# CapstoneMCU.net
KiCad netlist of a schematic drawn in EasyEDA Pro
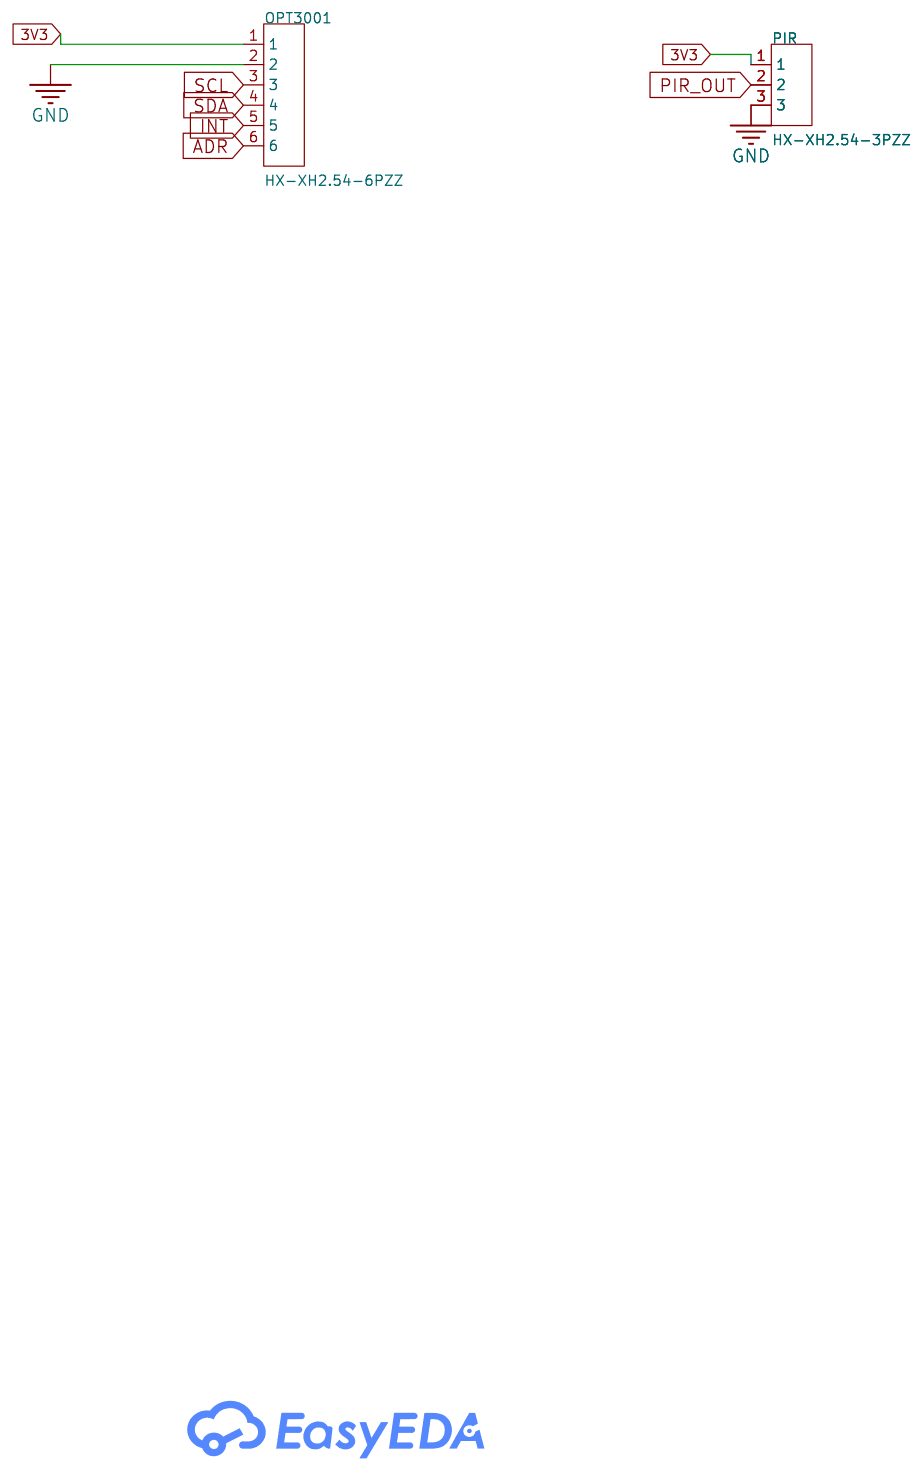
[diagram p0: sensors]
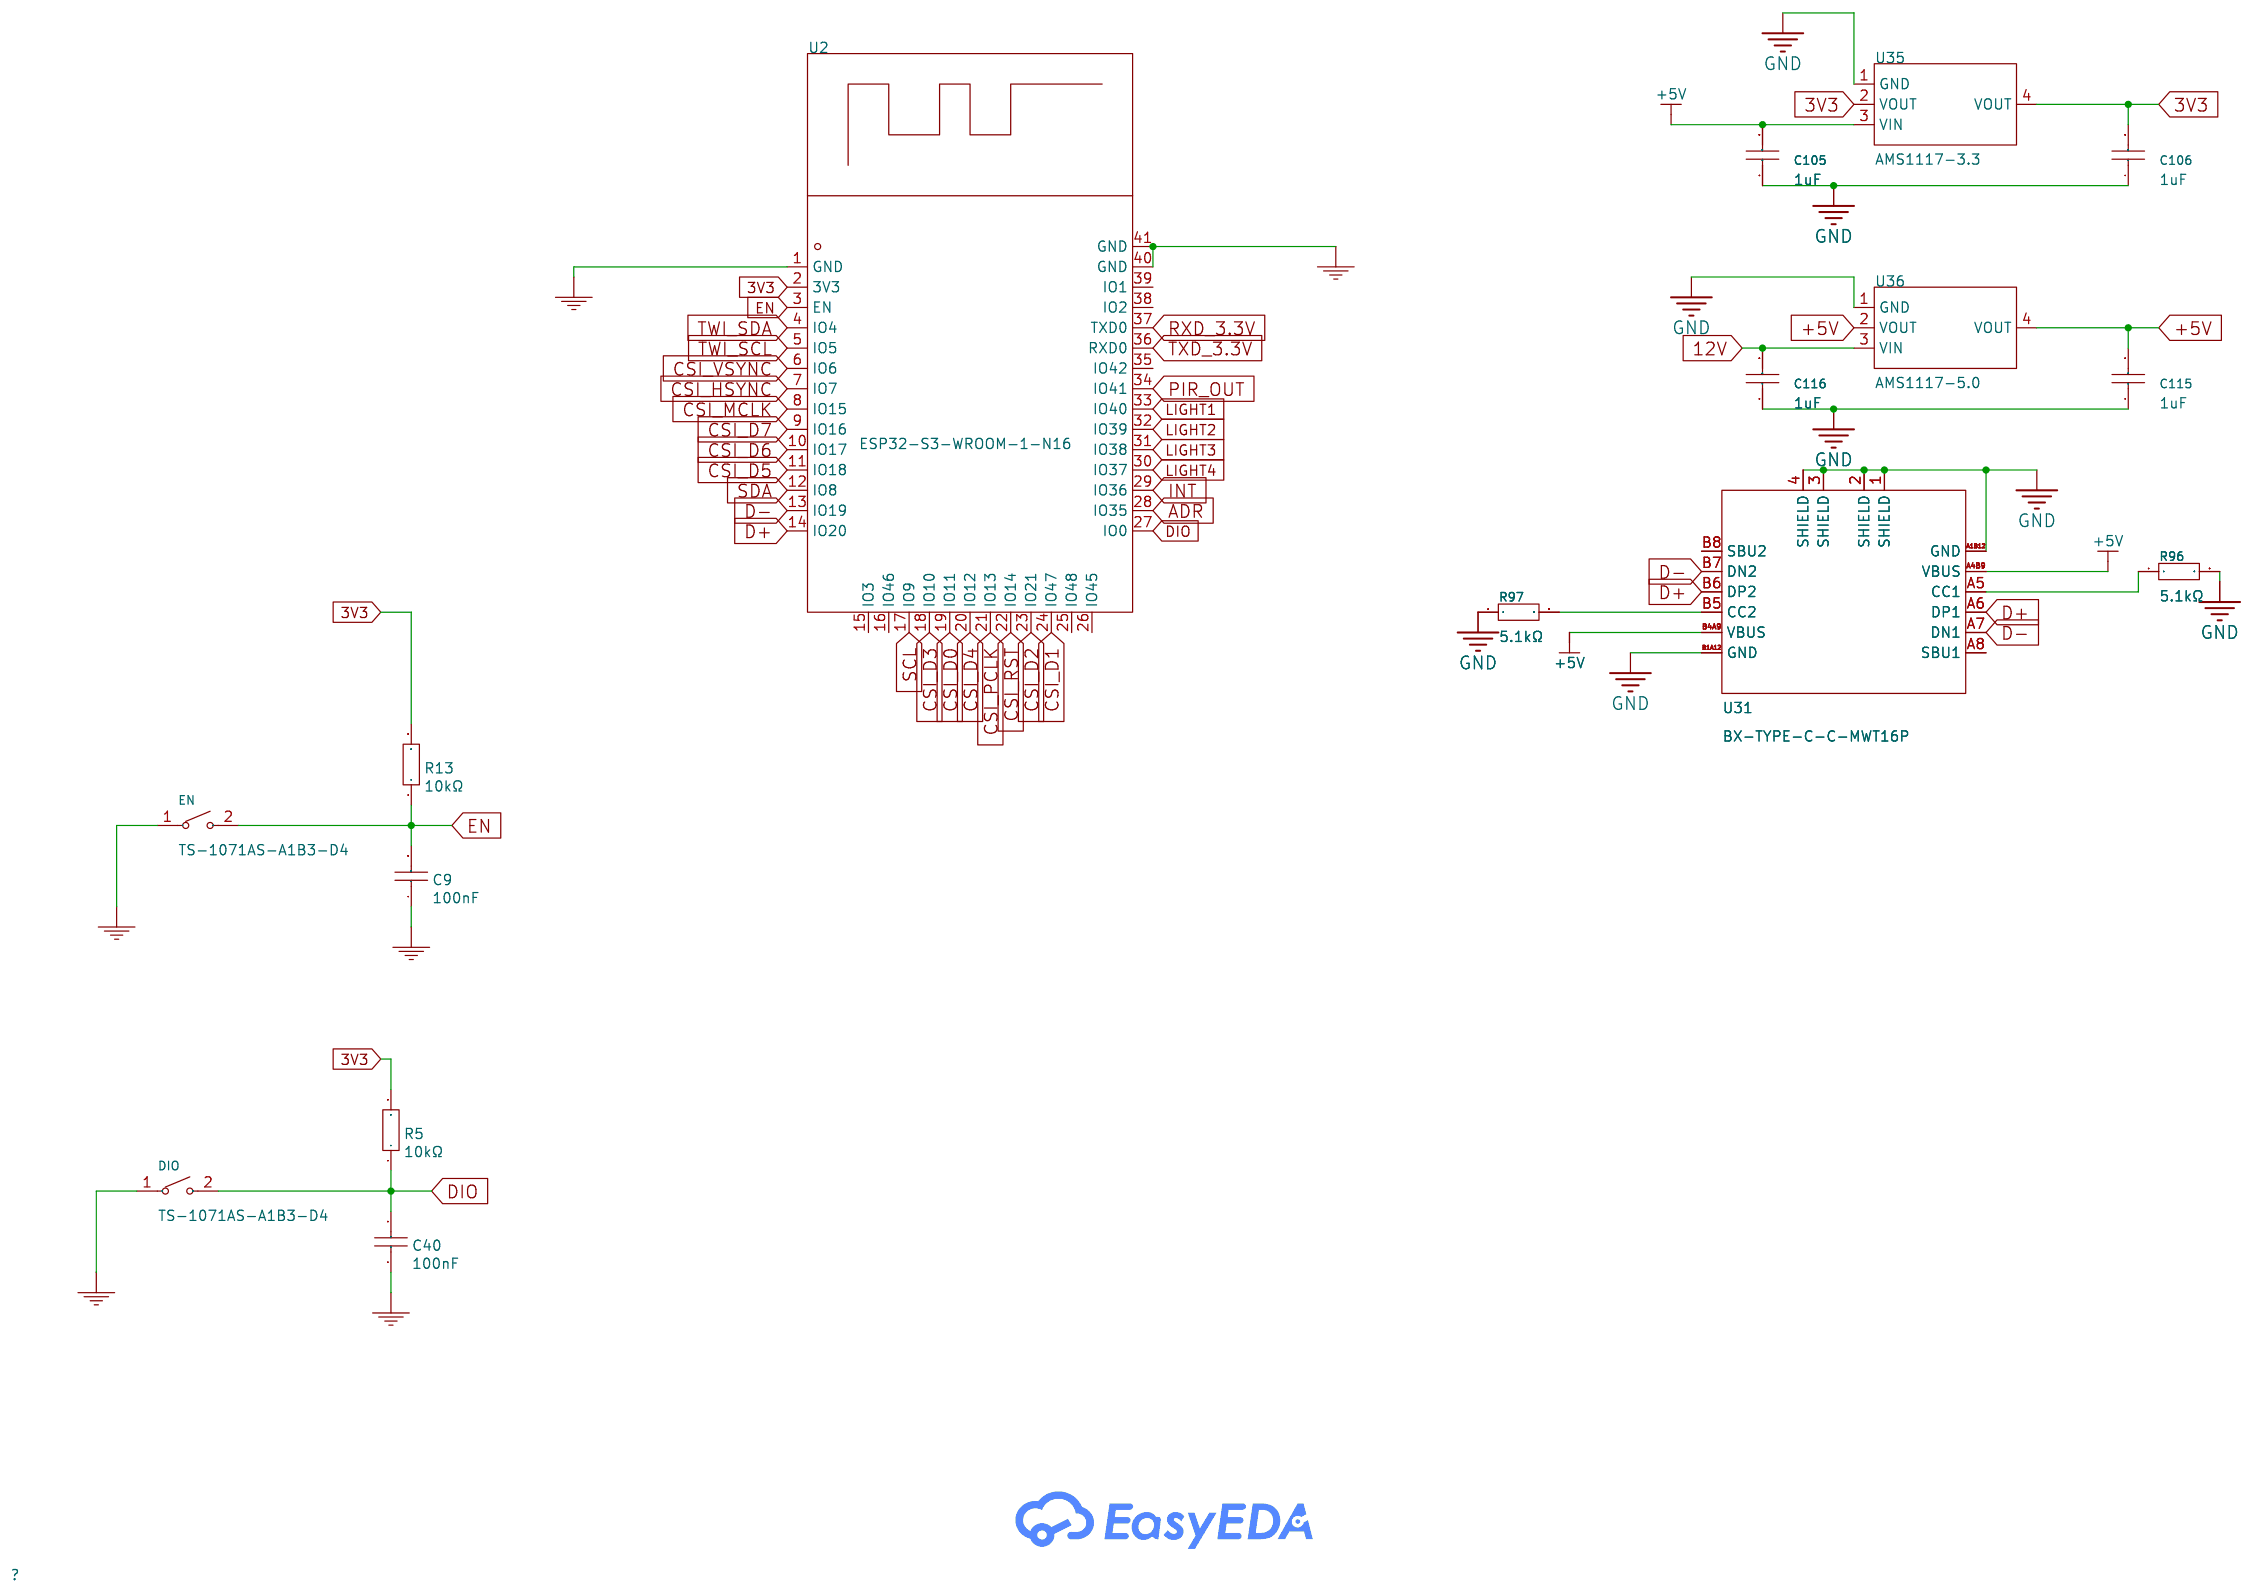
[diagram p1: ESP32-S3]
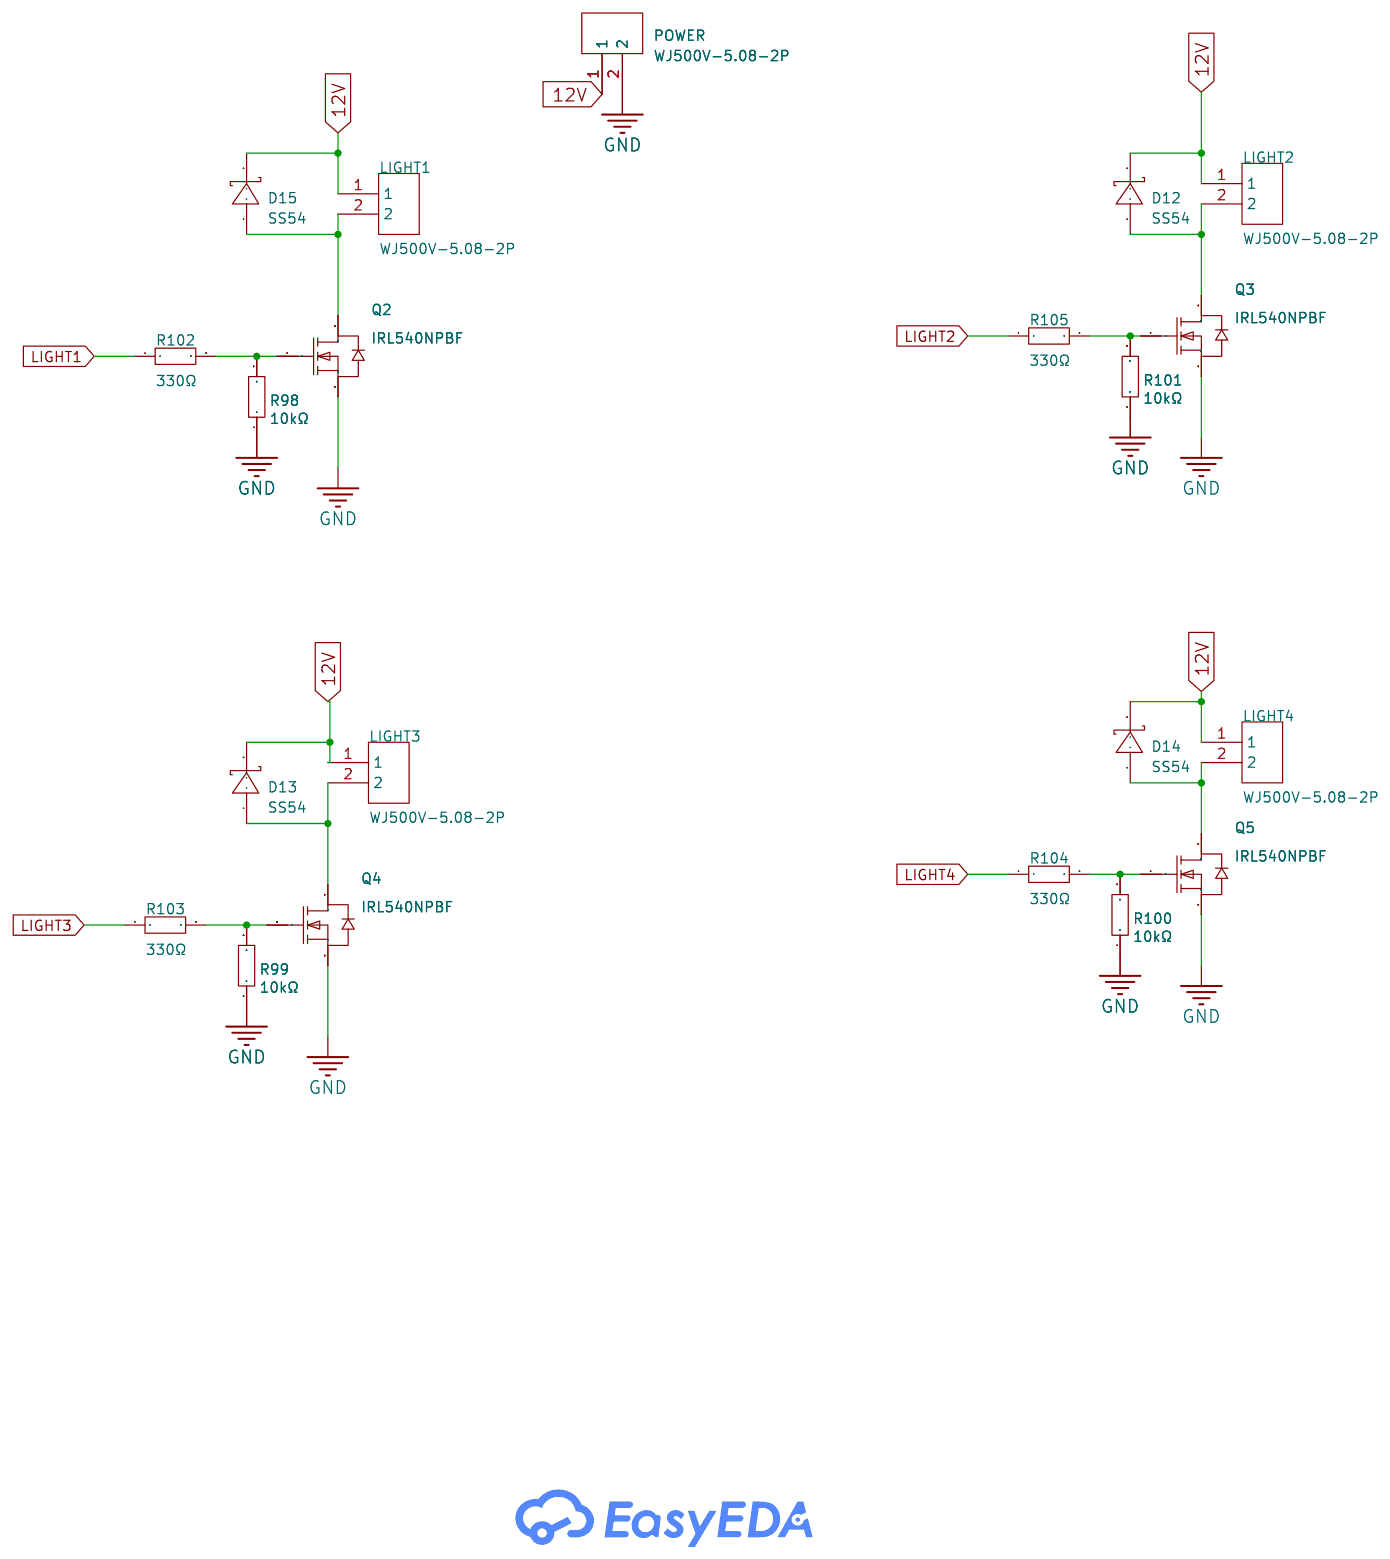
[diagram p2: MOSFET]
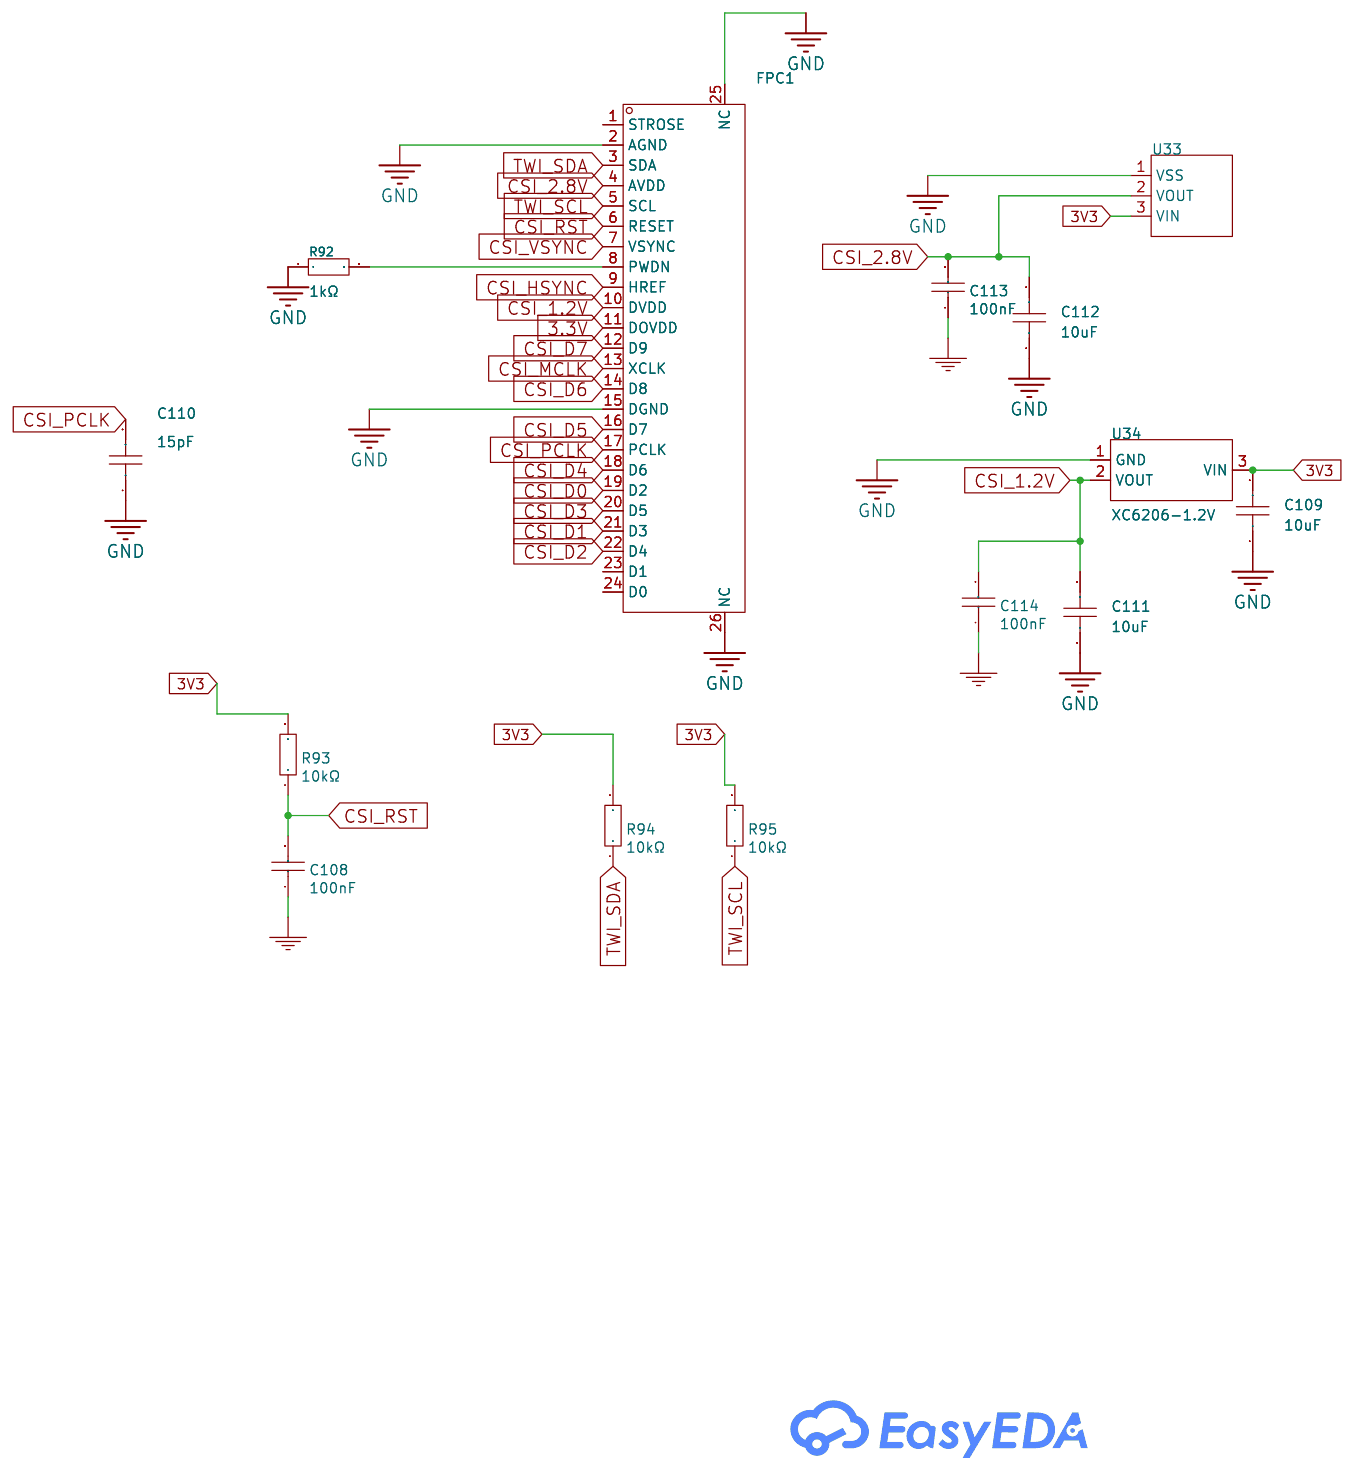
[diagram p3: camera]

(export (version "E")
  (design (tool "Eeschema 10.0.6"))
  (components
    (comp (ref "OPT3001")
      (value "HX-XH2.54-6PZZ")
      (footprint "easyedapro:CONN-TH_6P-P2.50_BX-XH2.54-6PZZ")
      (fields (field (name "Manufacturer") "hanxia(韩下)"))
      (libsource (lib "easyedapro") (part "HX-XH2.54-6PZZ"))
    )
    (comp (ref "PIR")
      (value "HX-XH2.54-3PZZ")
      (footprint "easyedapro:CONN-TH_3P-P2.50_HC-XH-3A-G")
      (fields (field (name "Manufacturer") "hanxia(韩下)"))
      (libsource (lib "easyedapro") (part "HX-XH2.54-3PZZ"))
    )
    (comp (ref "C9")
      (value "100nF")
      (footprint "easyedapro:C0402_NEW")
      (fields (field (name "Manufacturer Part") "CL05B104KO5NNNC") (field (name "Manufacturer") "SAMSUNG"))
      (libsource (lib "easyedapro") (part "100nF"))
    )
    (comp (ref "C40")
      (value "100nF")
      (footprint "easyedapro:C0402_NEW")
      (fields (field (name "Manufacturer Part") "CL05B104KO5NNNC") (field (name "Manufacturer") "SAMSUNG"))
      (libsource (lib "easyedapro") (part "100nF"))
    )
    (comp (ref "C105")
      (value "1uF")
      (footprint "easyedapro:C0402")
      (fields
        (field (name "Manufacturer Part") "CL05A105KP5NNNC")
        (field (name "Manufacturer") "SAMSUNG(三星)")
      )
      (libsource (lib "easyedapro") (part "CL05A105KP5NNNC"))
    )
    (comp (ref "C106")
      (value "1uF")
      (footprint "easyedapro:C0402")
      (fields
        (field (name "Manufacturer Part") "CL05A105KP5NNNC")
        (field (name "Manufacturer") "SAMSUNG(三星)")
      )
      (libsource (lib "easyedapro") (part "CL05A105KP5NNNC"))
    )
    (comp (ref "C115")
      (value "1uF")
      (footprint "easyedapro:C0402")
      (fields
        (field (name "Manufacturer Part") "CL05A105KP5NNNC")
        (field (name "Manufacturer") "SAMSUNG(三星)")
      )
      (libsource (lib "easyedapro") (part "CL05A105KP5NNNC"))
    )
    (comp (ref "C116")
      (value "1uF")
      (footprint "easyedapro:C0402")
      (fields
        (field (name "Manufacturer Part") "CL05A105KP5NNNC")
        (field (name "Manufacturer") "SAMSUNG(三星)")
      )
      (libsource (lib "easyedapro") (part "CL05A105KP5NNNC"))
    )
    (comp (ref "DIO")
      (value "TS-1071AS-A1B3-D4")
      (footprint "easyedapro:SW-SMD_L4.0-W3.0-LS4.8")
      (fields (field (name "Manufacturer") "Yuandi(元迪)"))
      (libsource (lib "easyedapro") (part "TS-1071AS-A1B3-D4"))
    )
    (comp (ref "EN")
      (value "TS-1071AS-A1B3-D4")
      (footprint "easyedapro:SW-SMD_L4.0-W3.0-LS4.8")
      (fields (field (name "Manufacturer") "Yuandi(元迪)"))
      (libsource (lib "easyedapro") (part "TS-1071AS-A1B3-D4"))
    )
    (comp (ref "R5")
      (value "10kΩ")
      (footprint "easyedapro:R0402")
      (fields (field (name "Manufacturer Part") "0402WGF1002TCE") (field (name "Manufacturer") "UniOhm"))
      (libsource (lib "easyedapro") (part "10kΩ"))
    )
    (comp (ref "R13")
      (value "10kΩ")
      (footprint "easyedapro:R0402")
      (fields (field (name "Manufacturer Part") "0402WGF1002TCE") (field (name "Manufacturer") "UniOhm"))
      (libsource (lib "easyedapro") (part "10kΩ"))
    )
    (comp (ref "R96")
      (value "5.1kΩ")
      (footprint "easyedapro:R0402")
      (fields
        (field (name "Manufacturer Part") "0402WGF5101TCE")
        (field (name "Manufacturer") "UNI-ROYAL(厚声)")
      )
      (libsource (lib "easyedapro") (part "0402WGF5101TCE"))
    )
    (comp (ref "R97")
      (value "5.1kΩ")
      (footprint "easyedapro:R0402")
      (fields
        (field (name "Manufacturer Part") "0402WGF5101TCE")
        (field (name "Manufacturer") "UNI-ROYAL(厚声)")
      )
      (libsource (lib "easyedapro") (part "0402WGF5101TCE"))
    )
    (comp (ref "U2")
      (value "ESP32-S3-WROOM-1-N16")
      (footprint "easyedapro:WIRELM-SMD_ESP32-S3-WROOM-1")
      (fields (field (name "Manufacturer") "ESPRESSIF(乐鑫)"))
      (libsource (lib "easyedapro") (part "ESP32-S3-WROOM-1(N16)"))
    )
    (comp (ref "U31")
      (value "BX-TYPE-C-C-MWT16P")
      (footprint "easyedapro:USB-C-SMD_BX-TYPE-C-C-MWT16P")
      (fields (field (name "Manufacturer") "Bossie(博锡)"))
      (libsource (lib "easyedapro") (part "BX-TYPE-C-C-MWT16P"))
    )
    (comp (ref "U35")
      (value "AMS1117-3.3")
      (footprint "easyedapro:SOT-223-3_L6.5-W3.4-P2.30-LS7.0-BR")
      (fields (field (name "Manufacturer") "AMS"))
      (libsource (lib "easyedapro") (part "AMS1117-3.3"))
    )
    (comp (ref "U36")
      (value "AMS1117-5.0")
      (footprint "easyedapro:SOT-223_L6.5-W3.5-P2.30-LS7.0-BR")
      (fields (field (name "Manufacturer") "AMS"))
      (libsource (lib "easyedapro") (part "AMS1117-5.0"))
    )
    (comp (ref "D12")
      (value "SS54")
      (footprint "easyedapro:SMA_L4.4-W2.8-LS5.4-R-RD")
      (fields (field (name "Manufacturer") "MDD(辰达半导体)"))
      (libsource (lib "easyedapro") (part "SS54_C22452"))
    )
    (comp (ref "D13")
      (value "SS54")
      (footprint "easyedapro:SMA_L4.4-W2.8-LS5.4-R-RD")
      (fields (field (name "Manufacturer") "MDD(辰达半导体)"))
      (libsource (lib "easyedapro") (part "SS54_C22452"))
    )
    (comp (ref "D14")
      (value "SS54")
      (footprint "easyedapro:SMA_L4.4-W2.8-LS5.4-R-RD")
      (fields (field (name "Manufacturer") "MDD(辰达半导体)"))
      (libsource (lib "easyedapro") (part "SS54_C22452"))
    )
    (comp (ref "D15")
      (value "SS54")
      (footprint "easyedapro:SMA_L4.4-W2.8-LS5.4-R-RD")
      (fields (field (name "Manufacturer") "MDD(辰达半导体)"))
      (libsource (lib "easyedapro") (part "SS54_C22452"))
    )
    (comp (ref "LIGHT1")
      (value "WJ500V-5.08-2P")
      (footprint "easyedapro:CONN-TH_2P-P5.00_WJ500V-5.08-2P")
      (fields (field (name "Manufacturer") "KANGNEX(康奈克斯电气)"))
      (libsource (lib "easyedapro") (part "WJ500V-5.08-2P-14-00A"))
    )
    (comp (ref "LIGHT2")
      (value "WJ500V-5.08-2P")
      (footprint "easyedapro:CONN-TH_2P-P5.00_WJ500V-5.08-2P")
      (fields (field (name "Manufacturer") "KANGNEX(康奈克斯电气)"))
      (libsource (lib "easyedapro") (part "WJ500V-5.08-2P-14-00A"))
    )
    (comp (ref "LIGHT3")
      (value "WJ500V-5.08-2P")
      (footprint "easyedapro:CONN-TH_2P-P5.00_WJ500V-5.08-2P")
      (fields (field (name "Manufacturer") "KANGNEX(康奈克斯电气)"))
      (libsource (lib "easyedapro") (part "WJ500V-5.08-2P-14-00A"))
    )
    (comp (ref "LIGHT4")
      (value "WJ500V-5.08-2P")
      (footprint "easyedapro:CONN-TH_2P-P5.00_WJ500V-5.08-2P")
      (fields (field (name "Manufacturer") "KANGNEX(康奈克斯电气)"))
      (libsource (lib "easyedapro") (part "WJ500V-5.08-2P-14-00A"))
    )
    (comp (ref "POWER")
      (value "WJ500V-5.08-2P")
      (footprint "easyedapro:CONN-TH_2P-P5.00_WJ500V-5.08-2P")
      (fields (field (name "Manufacturer") "KANGNEX(康奈克斯电气)"))
      (libsource (lib "easyedapro") (part "WJ500V-5.08-2P-14-00A"))
    )
    (comp (ref "Q2")
      (value "IRL540NPBF")
      (footprint "easyedapro:TO-220-3_L10.0-W4.5-P2.54-T")
      (fields (field (name "Manufacturer") "Infineon(英飞凌)"))
      (libsource (lib "easyedapro") (part "IRL540NPBF"))
    )
    (comp (ref "Q3")
      (value "IRL540NPBF")
      (footprint "easyedapro:TO-220-3_L10.0-W4.5-P2.54-T")
      (fields (field (name "Manufacturer") "Infineon(英飞凌)"))
      (libsource (lib "easyedapro") (part "IRL540NPBF"))
    )
    (comp (ref "Q4")
      (value "IRL540NPBF")
      (footprint "easyedapro:TO-220-3_L10.0-W4.5-P2.54-T")
      (fields (field (name "Manufacturer") "Infineon(英飞凌)"))
      (libsource (lib "easyedapro") (part "IRL540NPBF"))
    )
    (comp (ref "Q5")
      (value "IRL540NPBF")
      (footprint "easyedapro:TO-220-3_L10.0-W4.5-P2.54-T")
      (fields (field (name "Manufacturer") "Infineon(英飞凌)"))
      (libsource (lib "easyedapro") (part "IRL540NPBF"))
    )
    (comp (ref "R98")
      (value "10kΩ")
      (footprint "easyedapro:R0402")
      (fields (field (name "Manufacturer Part") "0402WGF1002TCE") (field (name "Manufacturer") "UniOhm"))
      (libsource (lib "easyedapro") (part "10kΩ"))
    )
    (comp (ref "R99")
      (value "10kΩ")
      (footprint "easyedapro:R0402")
      (fields (field (name "Manufacturer Part") "0402WGF1002TCE") (field (name "Manufacturer") "UniOhm"))
      (libsource (lib "easyedapro") (part "10kΩ"))
    )
    (comp (ref "R100")
      (value "10kΩ")
      (footprint "easyedapro:R0402")
      (fields (field (name "Manufacturer Part") "0402WGF1002TCE") (field (name "Manufacturer") "UniOhm"))
      (libsource (lib "easyedapro") (part "10kΩ"))
    )
    (comp (ref "R101")
      (value "10kΩ")
      (footprint "easyedapro:R0402")
      (fields (field (name "Manufacturer Part") "0402WGF1002TCE") (field (name "Manufacturer") "UniOhm"))
      (libsource (lib "easyedapro") (part "10kΩ"))
    )
    (comp (ref "R102")
      (value "330Ω")
      (footprint "easyedapro:R0402")
      (fields (field (name "Manufacturer Part") "RC0402FR-07330RL") (field (name "Manufacturer") "YAGEO(国巨)"))
      (libsource (lib "easyedapro") (part "RC0402FR-07330RL"))
    )
    (comp (ref "R103")
      (value "330Ω")
      (footprint "easyedapro:R0402")
      (fields (field (name "Manufacturer Part") "RC0402FR-07330RL") (field (name "Manufacturer") "YAGEO(国巨)"))
      (libsource (lib "easyedapro") (part "RC0402FR-07330RL"))
    )
    (comp (ref "R104")
      (value "330Ω")
      (footprint "easyedapro:R0402")
      (fields (field (name "Manufacturer Part") "RC0402FR-07330RL") (field (name "Manufacturer") "YAGEO(国巨)"))
      (libsource (lib "easyedapro") (part "RC0402FR-07330RL"))
    )
    (comp (ref "R105")
      (value "330Ω")
      (footprint "easyedapro:R0402")
      (fields (field (name "Manufacturer Part") "RC0402FR-07330RL") (field (name "Manufacturer") "YAGEO(国巨)"))
      (libsource (lib "easyedapro") (part "RC0402FR-07330RL"))
    )
    (comp (ref "C108")
      (value "100nF")
      (footprint "easyedapro:C0402_NEW")
      (fields (field (name "Manufacturer Part") "CL05B104KO5NNNC") (field (name "Manufacturer") "SAMSUNG"))
      (libsource (lib "easyedapro") (part "100nF"))
    )
    (comp (ref "C109")
      (value "10uF")
      (footprint "easyedapro:C0402")
      (description "Capacitance:10uF Tolerance:±20% Tolerance:±20% Voltage Rating:10V Temperature Coefficient:X5R")
      (fields
        (field (name "Manufacturer Part") "CL05A106MP5NUNC")
        (field (name "Manufacturer") "SAMSUNG(三星)")
      )
      (libsource (lib "easyedapro") (part "CL05A106MP5NUNC_C315248"))
    )
    (comp (ref "C110")
      (value "15pF")
      (footprint "easyedapro:C0402")
      (description "Capacitance:15pF Tolerance:±5% Tolerance:±5% Voltage Rating:50V Temperature Coefficient:C0G")
      (fields
        (field (name "Manufacturer Part") "CL05C150JB5NNNC")
        (field (name "Manufacturer") "SAMSUNG(三星)")
      )
      (libsource (lib "easyedapro") (part "CL05C150JB5NNNC"))
    )
    (comp (ref "C111")
      (value "10uF")
      (footprint "easyedapro:C0402")
      (description "Capacitance:10uF Tolerance:±20% Tolerance:±20% Voltage Rating:10V Temperature Coefficient:X5R")
      (fields
        (field (name "Manufacturer Part") "CL05A106MP5NUNC")
        (field (name "Manufacturer") "SAMSUNG(三星)")
      )
      (libsource (lib "easyedapro") (part "CL05A106MP5NUNC_C315248"))
    )
    (comp (ref "C112")
      (value "10uF")
      (footprint "easyedapro:C0402")
      (description "Capacitance:10uF Tolerance:±20% Tolerance:±20% Voltage Rating:10V Temperature Coefficient:X5R")
      (fields
        (field (name "Manufacturer Part") "CL05A106MP5NUNC")
        (field (name "Manufacturer") "SAMSUNG(三星)")
      )
      (libsource (lib "easyedapro") (part "CL05A106MP5NUNC_C315248"))
    )
    (comp (ref "C113")
      (value "100nF")
      (footprint "easyedapro:C0402_NEW")
      (fields (field (name "Manufacturer Part") "CL05B104KO5NNNC") (field (name "Manufacturer") "SAMSUNG"))
      (libsource (lib "easyedapro") (part "100nF"))
    )
    (comp (ref "C114")
      (value "100nF")
      (footprint "easyedapro:C0402_NEW")
      (fields (field (name "Manufacturer Part") "CL05B104KO5NNNC") (field (name "Manufacturer") "SAMSUNG"))
      (libsource (lib "easyedapro") (part "100nF"))
    )
    (comp (ref "FPC1")
      (value "~")
      (footprint "easyedapro:FPC-SMD_P0.50-24P_XJ-FGS")
      (libsource (lib "easyedapro") (part "OV2640"))
    )
    (comp (ref "R92")
      (value "1kΩ")
      (footprint "easyedapro:R0402")
      (fields
        (field (name "Manufacturer Part") "0402WGF1001TCE")
        (field (name "Manufacturer") "UNI-ROYAL(厚声)")
      )
      (libsource (lib "easyedapro") (part "0402WGF1001TCE"))
    )
    (comp (ref "R93")
      (value "10kΩ")
      (footprint "easyedapro:R0402")
      (fields (field (name "Manufacturer Part") "0402WGF1002TCE") (field (name "Manufacturer") "UniOhm"))
      (libsource (lib "easyedapro") (part "10kΩ"))
    )
    (comp (ref "R94")
      (value "10kΩ")
      (footprint "easyedapro:R0402")
      (fields (field (name "Manufacturer Part") "0402WGF1002TCE") (field (name "Manufacturer") "UniOhm"))
      (libsource (lib "easyedapro") (part "10kΩ"))
    )
    (comp (ref "R95")
      (value "10kΩ")
      (footprint "easyedapro:R0402")
      (fields (field (name "Manufacturer Part") "0402WGF1002TCE") (field (name "Manufacturer") "UniOhm"))
      (libsource (lib "easyedapro") (part "10kΩ"))
    )
    (comp (ref "U33")
      (value "XC6206-2.8V")
      (footprint "easyedapro:SOT-23-3_L2.9-W1.6-P1.90-LS2.8-BR")
      (fields (field (name "Manufacturer") "YONGYUTAI(永裕泰)"))
      (libsource (lib "easyedapro") (part "XC6206-2.8V"))
    )
    (comp (ref "U34")
      (value "XC6206-1.2V")
      (footprint "easyedapro:SOT-23-3_L3.0-W1.6-P1.90-LS2.8-BR")
      (fields (field (name "Manufacturer") "YONGYUTAI(永裕泰)"))
      (libsource (lib "easyedapro") (part "XC6206-1.2V_C49446790"))
    )
  )
  (nets
    (net (code "1") (name "+5V") (class "Default")
      (node (ref "C105") (pin "2") (pinfunction "2_2") (pintype "input"))
      (node (ref "C115") (pin "2") (pinfunction "2_2") (pintype "input"))
      (node (ref "U31") (pin "A4B9") (pinfunction "VBUS_A4B9") (pintype "unspecified"))
      (node (ref "U31") (pin "B4A9") (pinfunction "VBUS_B4A9") (pintype "unspecified"))
      (node (ref "U35") (pin "3") (pinfunction "VIN_3") (pintype "unspecified"))
      (node (ref "U36") (pin "2") (pinfunction "VOUT_2") (pintype "unspecified"))
      (node (ref "U36") (pin "4") (pinfunction "VOUT_4") (pintype "unspecified"))
    )
    (net (code "2") (name "3.3V") (class "Default")
      (node (ref "FPC1") (pin "11") (pinfunction "DOVDD_11") (pintype "input"))
    )
    (net (code "3") (name "3V3") (class "Default")
      (node (ref "C106") (pin "2") (pinfunction "2_2") (pintype "input"))
      (node (ref "C109") (pin "2") (pinfunction "2_2") (pintype "unspecified"))
      (node (ref "OPT3001") (pin "1") (pinfunction "1_1") (pintype "unspecified"))
      (node (ref "PIR") (pin "1") (pinfunction "1_1") (pintype "unspecified"))
      (node (ref "R13") (pin "2") (pinfunction "2_2") (pintype "input"))
      (node (ref "R5") (pin "2") (pinfunction "2_2") (pintype "input"))
      (node (ref "R93") (pin "2") (pinfunction "2_2") (pintype "input"))
      (node (ref "R94") (pin "2") (pinfunction "2_2") (pintype "input"))
      (node (ref "R95") (pin "2") (pinfunction "2_2") (pintype "input"))
      (node (ref "U2") (pin "2") (pinfunction "3V3_2") (pintype "unspecified"))
      (node (ref "U33") (pin "3") (pinfunction "VIN_3") (pintype "unspecified"))
      (node (ref "U34") (pin "3") (pinfunction "VIN_3") (pintype "unspecified"))
      (node (ref "U35") (pin "2") (pinfunction "VOUT_2") (pintype "unspecified"))
      (node (ref "U35") (pin "4") (pinfunction "VOUT_4") (pintype "unspecified"))
    )
    (net (code "4") (name "12V") (class "Default")
      (node (ref "C116") (pin "2") (pinfunction "2_2") (pintype "input"))
      (node (ref "D12") (pin "2") (pinfunction "K_2") (pintype "unspecified"))
      (node (ref "D13") (pin "2") (pinfunction "K_2") (pintype "unspecified"))
      (node (ref "D14") (pin "2") (pinfunction "K_2") (pintype "unspecified"))
      (node (ref "D15") (pin "2") (pinfunction "K_2") (pintype "unspecified"))
      (node (ref "LIGHT1") (pin "1") (pinfunction "1_1") (pintype "unspecified"))
      (node (ref "LIGHT2") (pin "1") (pinfunction "1_1") (pintype "unspecified"))
      (node (ref "LIGHT3") (pin "1") (pinfunction "1_1") (pintype "unspecified"))
      (node (ref "LIGHT4") (pin "1") (pinfunction "1_1") (pintype "unspecified"))
      (node (ref "POWER") (pin "1") (pinfunction "1_1") (pintype "unspecified"))
      (node (ref "U36") (pin "3") (pinfunction "VIN_3") (pintype "unspecified"))
    )
    (net (code "5") (name "ADR") (class "Default")
      (node (ref "OPT3001") (pin "6") (pinfunction "6_6") (pintype "unspecified"))
      (node (ref "U2") (pin "28") (pinfunction "IO35_28") (pintype "unspecified"))
    )
    (net (code "6") (name "CSI_1.2V") (class "Default")
      (node (ref "C111") (pin "2") (pinfunction "2_2") (pintype "unspecified"))
      (node (ref "C114") (pin "2") (pinfunction "2_2") (pintype "input"))
      (node (ref "FPC1") (pin "10") (pinfunction "DVDD_10") (pintype "input"))
      (node (ref "U34") (pin "2") (pinfunction "VOUT_2") (pintype "unspecified"))
    )
    (net (code "7") (name "CSI_2.8V") (class "Default")
      (node (ref "C112") (pin "2") (pinfunction "2_2") (pintype "unspecified"))
      (node (ref "C113") (pin "2") (pinfunction "2_2") (pintype "input"))
      (node (ref "FPC1") (pin "4") (pinfunction "AVDD_4") (pintype "input"))
      (node (ref "U33") (pin "2") (pinfunction "VOUT_2") (pintype "unspecified"))
    )
    (net (code "8") (name "CSI_D0") (class "Default")
      (node (ref "FPC1") (pin "19") (pinfunction "D2_19") (pintype "input"))
      (node (ref "U2") (pin "19") (pinfunction "IO11_19") (pintype "unspecified"))
    )
    (net (code "9") (name "CSI_D1") (class "Default")
      (node (ref "FPC1") (pin "21") (pinfunction "D3_21") (pintype "input"))
      (node (ref "U2") (pin "24") (pinfunction "IO47_24") (pintype "unspecified"))
    )
    (net (code "10") (name "CSI_D2") (class "Default")
      (node (ref "FPC1") (pin "22") (pinfunction "D4_22") (pintype "input"))
      (node (ref "U2") (pin "23") (pinfunction "IO21_23") (pintype "unspecified"))
    )
    (net (code "11") (name "CSI_D3") (class "Default")
      (node (ref "FPC1") (pin "20") (pinfunction "D5_20") (pintype "input"))
      (node (ref "U2") (pin "18") (pinfunction "IO10_18") (pintype "unspecified"))
    )
    (net (code "12") (name "CSI_D4") (class "Default")
      (node (ref "FPC1") (pin "18") (pinfunction "D6_18") (pintype "input"))
      (node (ref "U2") (pin "20") (pinfunction "IO12_20") (pintype "unspecified"))
    )
    (net (code "13") (name "CSI_D5") (class "Default")
      (node (ref "FPC1") (pin "16") (pinfunction "D7_16") (pintype "input"))
      (node (ref "U2") (pin "11") (pinfunction "IO18_11") (pintype "unspecified"))
    )
    (net (code "14") (name "CSI_D6") (class "Default")
      (node (ref "FPC1") (pin "14") (pinfunction "D8_14") (pintype "input"))
      (node (ref "U2") (pin "10") (pinfunction "IO17_10") (pintype "unspecified"))
    )
    (net (code "15") (name "CSI_D7") (class "Default")
      (node (ref "FPC1") (pin "12") (pinfunction "D9_12") (pintype "input"))
      (node (ref "U2") (pin "9") (pinfunction "IO16_9") (pintype "unspecified"))
    )
    (net (code "16") (name "CSI_HSYNC") (class "Default")
      (node (ref "FPC1") (pin "9") (pinfunction "HREF_9") (pintype "input"))
      (node (ref "U2") (pin "7") (pinfunction "IO7_7") (pintype "unspecified"))
    )
    (net (code "17") (name "CSI_MCLK") (class "Default")
      (node (ref "FPC1") (pin "13") (pinfunction "XCLK_13") (pintype "input"))
      (node (ref "U2") (pin "8") (pinfunction "IO15_8") (pintype "unspecified"))
    )
    (net (code "18") (name "CSI_PCLK") (class "Default")
      (node (ref "C110") (pin "2") (pinfunction "2_2") (pintype "unspecified"))
      (node (ref "FPC1") (pin "17") (pinfunction "PCLK_17") (pintype "input"))
      (node (ref "U2") (pin "21") (pinfunction "IO13_21") (pintype "unspecified"))
    )
    (net (code "19") (name "CSI_RST") (class "Default")
      (node (ref "C108") (pin "2") (pinfunction "2_2") (pintype "input"))
      (node (ref "FPC1") (pin "6") (pinfunction "RESET_6") (pintype "input"))
      (node (ref "R93") (pin "1") (pinfunction "1_1") (pintype "input"))
      (node (ref "U2") (pin "22") (pinfunction "IO14_22") (pintype "unspecified"))
    )
    (net (code "20") (name "CSI_VSYNC") (class "Default")
      (node (ref "FPC1") (pin "7") (pinfunction "VSYNC_7") (pintype "input"))
      (node (ref "U2") (pin "6") (pinfunction "IO6_6") (pintype "unspecified"))
    )
    (net (code "21") (name "D+") (class "Default")
      (node (ref "U2") (pin "14") (pinfunction "IO20_14") (pintype "unspecified"))
      (node (ref "U31") (pin "A6") (pinfunction "DP1_A6") (pintype "unspecified"))
      (node (ref "U31") (pin "B6") (pinfunction "DP2_B6") (pintype "unspecified"))
    )
    (net (code "22") (name "D-") (class "Default")
      (node (ref "U2") (pin "13") (pinfunction "IO19_13") (pintype "unspecified"))
      (node (ref "U31") (pin "A7") (pinfunction "DN1_A7") (pintype "unspecified"))
      (node (ref "U31") (pin "B7") (pinfunction "DN2_B7") (pintype "unspecified"))
    )
    (net (code "23") (name "DIO") (class "Default")
      (node (ref "C40") (pin "2") (pinfunction "2_2") (pintype "input"))
      (node (ref "DIO") (pin "2") (pinfunction "2_2") (pintype "input"))
      (node (ref "R5") (pin "1") (pinfunction "1_1") (pintype "input"))
      (node (ref "U2") (pin "27") (pinfunction "IO0_27") (pintype "unspecified"))
    )
    (net (code "24") (name "EN") (class "Default")
      (node (ref "C9") (pin "2") (pinfunction "2_2") (pintype "input"))
      (node (ref "EN") (pin "2") (pinfunction "2_2") (pintype "input"))
      (node (ref "R13") (pin "1") (pinfunction "1_1") (pintype "input"))
      (node (ref "U2") (pin "3") (pinfunction "EN_3") (pintype "unspecified"))
    )
    (net (code "25") (name "GND") (class "Default")
      (node (ref "C105") (pin "1") (pinfunction "1_1") (pintype "input"))
      (node (ref "C106") (pin "1") (pinfunction "1_1") (pintype "input"))
      (node (ref "C108") (pin "1") (pinfunction "1_1") (pintype "input"))
      (node (ref "C109") (pin "1") (pinfunction "1_1") (pintype "unspecified"))
      (node (ref "C110") (pin "1") (pinfunction "1_1") (pintype "unspecified"))
      (node (ref "C111") (pin "1") (pinfunction "1_1") (pintype "unspecified"))
      (node (ref "C112") (pin "1") (pinfunction "1_1") (pintype "unspecified"))
      (node (ref "C113") (pin "1") (pinfunction "1_1") (pintype "input"))
      (node (ref "C114") (pin "1") (pinfunction "1_1") (pintype "input"))
      (node (ref "C115") (pin "1") (pinfunction "1_1") (pintype "input"))
      (node (ref "C116") (pin "1") (pinfunction "1_1") (pintype "input"))
      (node (ref "C40") (pin "1") (pinfunction "1_1") (pintype "input"))
      (node (ref "C9") (pin "1") (pinfunction "1_1") (pintype "input"))
      (node (ref "DIO") (pin "1") (pinfunction "1_1") (pintype "input"))
      (node (ref "EN") (pin "1") (pinfunction "1_1") (pintype "input"))
      (node (ref "FPC1") (pin "15") (pinfunction "DGND_15") (pintype "input"))
      (node (ref "FPC1") (pin "2") (pinfunction "AGND_2") (pintype "input"))
      (node (ref "FPC1") (pin "25") (pinfunction "NC_25") (pintype "input"))
      (node (ref "FPC1") (pin "26") (pinfunction "NC_26") (pintype "input"))
      (node (ref "OPT3001") (pin "2") (pinfunction "2_2") (pintype "unspecified"))
      (node (ref "PIR") (pin "3") (pinfunction "3_3") (pintype "unspecified"))
      (node (ref "POWER") (pin "2") (pinfunction "2_2") (pintype "unspecified"))
      (node (ref "Q2") (pin "3") (pinfunction "S_3") (pintype "unspecified"))
      (node (ref "Q3") (pin "3") (pinfunction "S_3") (pintype "unspecified"))
      (node (ref "Q4") (pin "3") (pinfunction "S_3") (pintype "unspecified"))
      (node (ref "Q5") (pin "3") (pinfunction "S_3") (pintype "unspecified"))
      (node (ref "R100") (pin "1") (pinfunction "1_1") (pintype "input"))
      (node (ref "R101") (pin "1") (pinfunction "1_1") (pintype "input"))
      (node (ref "R92") (pin "1") (pinfunction "1_1") (pintype "input"))
      (node (ref "R96") (pin "2") (pinfunction "2_2") (pintype "input"))
      (node (ref "R97") (pin "1") (pinfunction "1_1") (pintype "input"))
      (node (ref "R98") (pin "1") (pinfunction "1_1") (pintype "input"))
      (node (ref "R99") (pin "1") (pinfunction "1_1") (pintype "input"))
      (node (ref "U2") (pin "1") (pinfunction "GND_1") (pintype "unspecified"))
      (node (ref "U2") (pin "40") (pinfunction "GND_40") (pintype "unspecified"))
      (node (ref "U2") (pin "41") (pinfunction "GND_41") (pintype "unspecified"))
      (node (ref "U31") (pin "1") (pinfunction "SHIELD_1") (pintype "unspecified"))
      (node (ref "U31") (pin "2") (pinfunction "SHIELD_2") (pintype "unspecified"))
      (node (ref "U31") (pin "3") (pinfunction "SHIELD_3") (pintype "unspecified"))
      (node (ref "U31") (pin "4") (pinfunction "SHIELD_4") (pintype "unspecified"))
      (node (ref "U31") (pin "A1B12") (pinfunction "GND_A1B12") (pintype "unspecified"))
      (node (ref "U31") (pin "B1A12") (pinfunction "GND_B1A12") (pintype "unspecified"))
      (node (ref "U33") (pin "1") (pinfunction "VSS_1") (pintype "unspecified"))
      (node (ref "U34") (pin "1") (pinfunction "GND_1") (pintype "unspecified"))
      (node (ref "U35") (pin "1") (pinfunction "GND_1") (pintype "unspecified"))
      (node (ref "U36") (pin "1") (pinfunction "GND_1") (pintype "unspecified"))
    )
    (net (code "26") (name "INT") (class "Default")
      (node (ref "OPT3001") (pin "5") (pinfunction "5_5") (pintype "unspecified"))
      (node (ref "U2") (pin "29") (pinfunction "IO36_29") (pintype "unspecified"))
    )
    (net (code "27") (name "LIGHT1") (class "Default")
      (node (ref "R102") (pin "1") (pinfunction "1_1") (pintype "input"))
      (node (ref "U2") (pin "33") (pinfunction "IO40_33") (pintype "unspecified"))
    )
    (net (code "28") (name "LIGHT2") (class "Default")
      (node (ref "R105") (pin "1") (pinfunction "1_1") (pintype "input"))
      (node (ref "U2") (pin "32") (pinfunction "IO39_32") (pintype "unspecified"))
    )
    (net (code "29") (name "LIGHT3") (class "Default")
      (node (ref "R103") (pin "1") (pinfunction "1_1") (pintype "input"))
      (node (ref "U2") (pin "31") (pinfunction "IO38_31") (pintype "unspecified"))
    )
    (net (code "30") (name "LIGHT4") (class "Default")
      (node (ref "R104") (pin "1") (pinfunction "1_1") (pintype "input"))
      (node (ref "U2") (pin "30") (pinfunction "IO37_30") (pintype "unspecified"))
    )
    (net (code "31") (name "Net-(D12-A)") (class "Default")
      (node (ref "D12") (pin "1") (pinfunction "A_1") (pintype "unspecified"))
      (node (ref "LIGHT2") (pin "2") (pinfunction "2_2") (pintype "unspecified"))
      (node (ref "Q3") (pin "2") (pinfunction "D_2") (pintype "unspecified"))
    )
    (net (code "32") (name "Net-(D13-A)") (class "Default")
      (node (ref "D13") (pin "1") (pinfunction "A_1") (pintype "unspecified"))
      (node (ref "LIGHT3") (pin "2") (pinfunction "2_2") (pintype "unspecified"))
      (node (ref "Q4") (pin "2") (pinfunction "D_2") (pintype "unspecified"))
    )
    (net (code "33") (name "Net-(D14-A)") (class "Default")
      (node (ref "D14") (pin "1") (pinfunction "A_1") (pintype "unspecified"))
      (node (ref "LIGHT4") (pin "2") (pinfunction "2_2") (pintype "unspecified"))
      (node (ref "Q5") (pin "2") (pinfunction "D_2") (pintype "unspecified"))
    )
    (net (code "34") (name "Net-(D15-A)") (class "Default")
      (node (ref "D15") (pin "1") (pinfunction "A_1") (pintype "unspecified"))
      (node (ref "LIGHT1") (pin "2") (pinfunction "2_2") (pintype "unspecified"))
      (node (ref "Q2") (pin "2") (pinfunction "D_2") (pintype "unspecified"))
    )
    (net (code "35") (name "Net-(FPC1-PWDN)") (class "Default")
      (node (ref "FPC1") (pin "8") (pinfunction "PWDN_8") (pintype "input"))
      (node (ref "R92") (pin "2") (pinfunction "2_2") (pintype "input"))
    )
    (net (code "36") (name "Net-(Q2-G)") (class "Default")
      (node (ref "Q2") (pin "1") (pinfunction "G_1") (pintype "unspecified"))
      (node (ref "R102") (pin "2") (pinfunction "2_2") (pintype "input"))
      (node (ref "R98") (pin "2") (pinfunction "2_2") (pintype "input"))
    )
    (net (code "37") (name "Net-(Q3-G)") (class "Default")
      (node (ref "Q3") (pin "1") (pinfunction "G_1") (pintype "unspecified"))
      (node (ref "R101") (pin "2") (pinfunction "2_2") (pintype "input"))
      (node (ref "R105") (pin "2") (pinfunction "2_2") (pintype "input"))
    )
    (net (code "38") (name "Net-(Q4-G)") (class "Default")
      (node (ref "Q4") (pin "1") (pinfunction "G_1") (pintype "unspecified"))
      (node (ref "R103") (pin "2") (pinfunction "2_2") (pintype "input"))
      (node (ref "R99") (pin "2") (pinfunction "2_2") (pintype "input"))
    )
    (net (code "39") (name "Net-(Q5-G)") (class "Default")
      (node (ref "Q5") (pin "1") (pinfunction "G_1") (pintype "unspecified"))
      (node (ref "R100") (pin "2") (pinfunction "2_2") (pintype "input"))
      (node (ref "R104") (pin "2") (pinfunction "2_2") (pintype "input"))
    )
    (net (code "40") (name "Net-(U31-CC1)") (class "Default")
      (node (ref "R96") (pin "1") (pinfunction "1_1") (pintype "input"))
      (node (ref "U31") (pin "A5") (pinfunction "CC1_A5") (pintype "unspecified"))
    )
    (net (code "41") (name "Net-(U31-CC2)") (class "Default")
      (node (ref "R97") (pin "2") (pinfunction "2_2") (pintype "input"))
      (node (ref "U31") (pin "B5") (pinfunction "CC2_B5") (pintype "unspecified"))
    )
    (net (code "42") (name "PIR_OUT") (class "Default")
      (node (ref "PIR") (pin "2") (pinfunction "2_2") (pintype "unspecified"))
      (node (ref "U2") (pin "34") (pinfunction "IO41_34") (pintype "unspecified"))
    )
    (net (code "43") (name "RXD_3.3V") (class "Default")
      (node (ref "U2") (pin "37") (pinfunction "TXD0_37") (pintype "unspecified"))
    )
    (net (code "44") (name "SCL") (class "Default")
      (node (ref "OPT3001") (pin "3") (pinfunction "3_3") (pintype "unspecified"))
      (node (ref "U2") (pin "17") (pinfunction "IO9_17") (pintype "unspecified"))
    )
    (net (code "45") (name "SDA") (class "Default")
      (node (ref "OPT3001") (pin "4") (pinfunction "4_4") (pintype "unspecified"))
      (node (ref "U2") (pin "12") (pinfunction "IO8_12") (pintype "unspecified"))
    )
    (net (code "46") (name "TWI_SCL") (class "Default")
      (node (ref "FPC1") (pin "5") (pinfunction "SCL_5") (pintype "input"))
      (node (ref "R95") (pin "1") (pinfunction "1_1") (pintype "input"))
      (node (ref "U2") (pin "5") (pinfunction "IO5_5") (pintype "unspecified"))
    )
    (net (code "47") (name "TWI_SDA") (class "Default")
      (node (ref "FPC1") (pin "3") (pinfunction "SDA_3") (pintype "input"))
      (node (ref "R94") (pin "1") (pinfunction "1_1") (pintype "input"))
      (node (ref "U2") (pin "4") (pinfunction "IO4_4") (pintype "unspecified"))
    )
    (net (code "48") (name "TXD_3.3V") (class "Default")
      (node (ref "U2") (pin "36") (pinfunction "RXD0_36") (pintype "unspecified"))
    )
    (net (code "49") (name "unconnected-(FPC1-D0-Pad24)") (class "Default")
      (node (ref "FPC1") (pin "24") (pinfunction "D0_24") (pintype "input"))
    )
    (net (code "50") (name "unconnected-(FPC1-D1-Pad23)") (class "Default")
      (node (ref "FPC1") (pin "23") (pinfunction "D1_23") (pintype "input"))
    )
    (net (code "51") (name "unconnected-(FPC1-STROSE-Pad1)") (class "Default")
      (node (ref "FPC1") (pin "1") (pinfunction "STROSE_1") (pintype "input"))
    )
    (net (code "52") (name "unconnected-(U2-IO1-Pad39)") (class "Default")
      (node (ref "U2") (pin "39") (pinfunction "IO1_39") (pintype "unspecified"))
    )
    (net (code "53") (name "unconnected-(U2-IO2-Pad38)") (class "Default")
      (node (ref "U2") (pin "38") (pinfunction "IO2_38") (pintype "unspecified"))
    )
    (net (code "54") (name "unconnected-(U2-IO3-Pad15)") (class "Default")
      (node (ref "U2") (pin "15") (pinfunction "IO3_15") (pintype "unspecified"))
    )
    (net (code "55") (name "unconnected-(U2-IO42-Pad35)") (class "Default")
      (node (ref "U2") (pin "35") (pinfunction "IO42_35") (pintype "unspecified"))
    )
    (net (code "56") (name "unconnected-(U2-IO45-Pad26)") (class "Default")
      (node (ref "U2") (pin "26") (pinfunction "IO45_26") (pintype "unspecified"))
    )
    (net (code "57") (name "unconnected-(U2-IO46-Pad16)") (class "Default")
      (node (ref "U2") (pin "16") (pinfunction "IO46_16") (pintype "unspecified"))
    )
    (net (code "58") (name "unconnected-(U2-IO48-Pad25)") (class "Default")
      (node (ref "U2") (pin "25") (pinfunction "IO48_25") (pintype "unspecified"))
    )
    (net (code "59") (name "unconnected-(U31-SBU1-PadA8)") (class "Default")
      (node (ref "U31") (pin "A8") (pinfunction "SBU1_A8") (pintype "unspecified"))
    )
    (net (code "60") (name "unconnected-(U31-SBU2-PadB8)") (class "Default")
      (node (ref "U31") (pin "B8") (pinfunction "SBU2_B8") (pintype "unspecified"))
    )
  )
)
